# SparkFun_HX711_Load_Cell.net
KiCad netlist of a schematic drawn in EAGLE
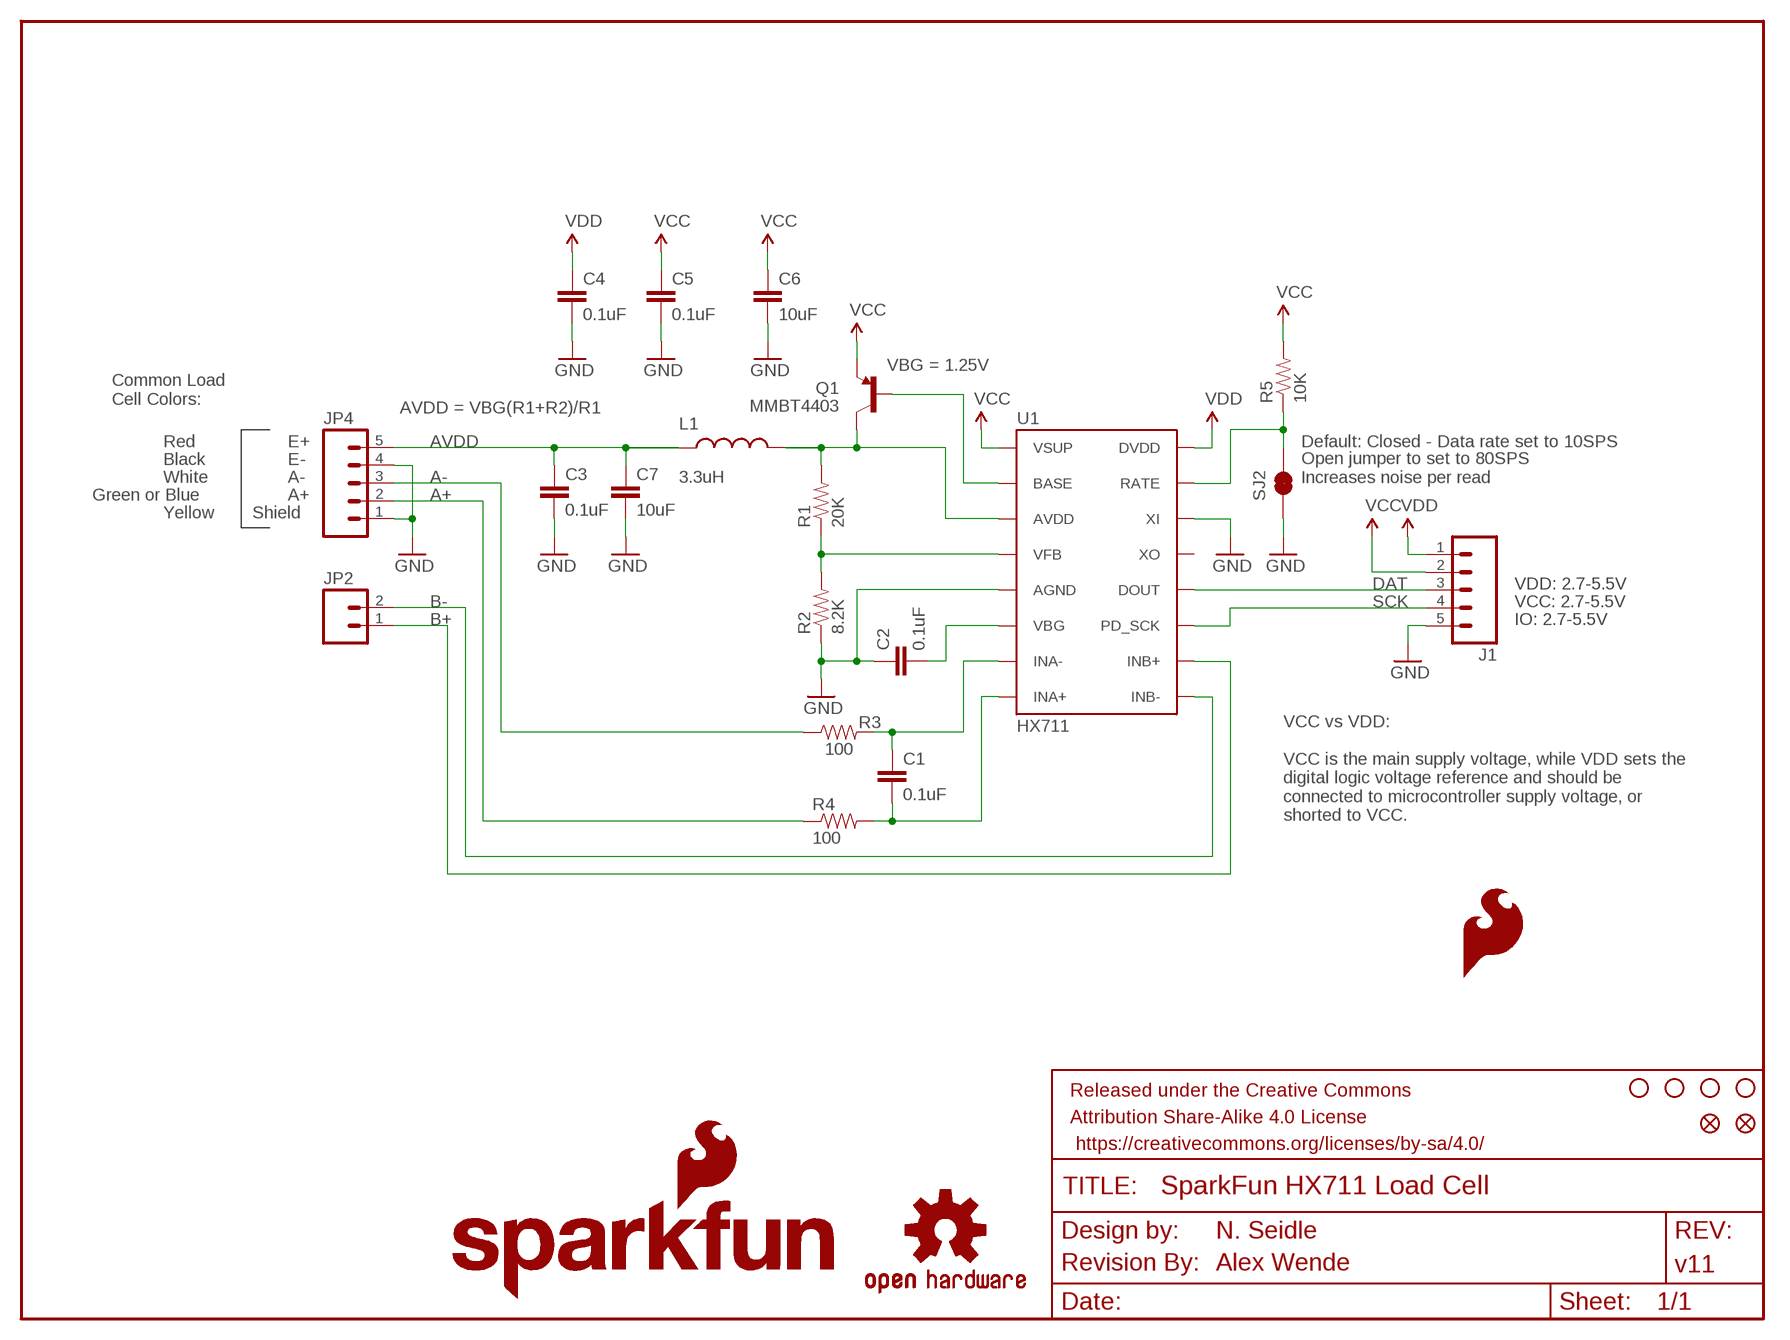
[diagram p0: schematic, sheet 1]

(export (version "E")
  (design (tool "Eeschema 10.0.6"))
  (components
    (comp (ref "C1")
      (value "0.1uF")
      (footprint "eagle-import:0603-CAP")
      (libsource (lib "eagle-import") (part "0.1UF-25V-5%(0603)"))
    )
    (comp (ref "C2")
      (value "0.1uF")
      (footprint "eagle-import:0603-CAP")
      (libsource (lib "eagle-import") (part "0.1UF-25V-5%(0603)"))
    )
    (comp (ref "C3")
      (value "0.1uF")
      (footprint "eagle-import:0603-CAP")
      (libsource (lib "eagle-import") (part "0.1UF-25V-5%(0603)"))
    )
    (comp (ref "C4")
      (value "0.1uF")
      (footprint "eagle-import:0603-CAP")
      (libsource (lib "eagle-import") (part "0.1UF-25V-5%(0603)"))
    )
    (comp (ref "C5")
      (value "0.1uF")
      (footprint "eagle-import:0603-CAP")
      (libsource (lib "eagle-import") (part "0.1UF-25V-5%(0603)"))
    )
    (comp (ref "C6")
      (value "10uF")
      (footprint "eagle-import:1210")
      (libsource (lib "eagle-import") (part "10UF50V20%(1210)"))
    )
    (comp (ref "C7")
      (value "10uF")
      (footprint "eagle-import:1210")
      (libsource (lib "eagle-import") (part "10UF50V20%(1210)"))
    )
    (comp (ref "FID1")
      (value "FIDUCIAL1X2")
      (footprint "eagle-import:FIDUCIAL-1X2")
      (libsource (lib "eagle-import") (part "FIDUCIAL1X2"))
    )
    (comp (ref "FID2")
      (value "FIDUCIAL1X2")
      (footprint "eagle-import:FIDUCIAL-1X2")
      (libsource (lib "eagle-import") (part "FIDUCIAL1X2"))
    )
    (comp (ref "FRAME1")
      (value "FRAME-LETTER")
      (footprint "eagle-import:CREATIVE_COMMONS")
      (fields (field (name "DESIGNER") "N. Seidle") (field (name "VERSION") "v11"))
      (libsource (lib "eagle-import") (part "FRAME-LETTER"))
    )
    (comp (ref "J1")
      (value "M05PTH")
      (footprint "eagle-import:1X05")
      (libsource (lib "eagle-import") (part "M05PTH"))
    )
    (comp (ref "JP2")
      (value "M02PTH")
      (footprint "eagle-import:1X02")
      (libsource (lib "eagle-import") (part "M02PTH"))
    )
    (comp (ref "JP4")
      (value "M05PTH")
      (footprint "eagle-import:1X05")
      (libsource (lib "eagle-import") (part "M05PTH"))
    )
    (comp (ref "L1")
      (value "3.3uH")
      (footprint "eagle-import:0805")
      (libsource (lib "eagle-import") (part "INDUCTOR0805-IND"))
    )
    (comp (ref "LOGO1")
      (value "SFE_LOGO_NAME_FLAME.1_INCH")
      (footprint "eagle-import:SFE_LOGO_NAME_FLAME_.1")
      (libsource (lib "eagle-import") (part "SFE_LOGO_NAME_FLAME.1_INCH"))
    )
    (comp (ref "LOGO3")
      (value "SFE_LOGO_FLAME.1_INCH")
      (footprint "eagle-import:SFE_LOGO_FLAME_.1")
      (libsource (lib "eagle-import") (part "SFE_LOGO_FLAME.1_INCH"))
    )
    (comp (ref "Q1")
      (value "MMBT4403")
      (footprint "eagle-import:SOT23-3")
      (libsource (lib "eagle-import") (part "TRANSISTOR_PNPMMBT4403"))
    )
    (comp (ref "R1")
      (value "20K")
      (footprint "eagle-import:0603-RES")
      (libsource (lib "eagle-import") (part "20KOHM1/10W1%(0603)"))
    )
    (comp (ref "R2")
      (value "8.2K")
      (footprint "eagle-import:0603-RES")
      (libsource (lib "eagle-import") (part "8.2KOHM-1/10W-5%(0603)"))
    )
    (comp (ref "R3")
      (value "100")
      (footprint "eagle-import:0603-RES")
      (libsource (lib "eagle-import") (part "100OHM-1/10W-1%(0603)"))
    )
    (comp (ref "R4")
      (value "100")
      (footprint "eagle-import:0603-RES")
      (libsource (lib "eagle-import") (part "100OHM-1/10W-1%(0603)"))
    )
    (comp (ref "R5")
      (value "10K")
      (footprint "eagle-import:0603-RES")
      (libsource (lib "eagle-import") (part "10KOHM-1/10W-1%(0603)0603"))
    )
    (comp (ref "SJ2")
      (value "JUMPER-PAD-2-NC_BY_TRACE")
      (footprint "eagle-import:PAD-JUMPER-2-NC_BY_TRACE_YES_SILK")
      (libsource (lib "eagle-import") (part "JUMPER-PAD-2-NC_BY_TRACE"))
    )
    (comp (ref "STANDOFF1")
      (value "STAND-OFF")
      (footprint "eagle-import:STAND-OFF")
      (libsource (lib "eagle-import") (part "STAND-OFF"))
    )
    (comp (ref "STANDOFF2")
      (value "STAND-OFF")
      (footprint "eagle-import:STAND-OFF")
      (libsource (lib "eagle-import") (part "STAND-OFF"))
    )
    (comp (ref "STANDOFF3")
      (value "STAND-OFF")
      (footprint "eagle-import:STAND-OFF")
      (libsource (lib "eagle-import") (part "STAND-OFF"))
    )
    (comp (ref "STANDOFF4")
      (value "STAND-OFF")
      (footprint "eagle-import:STAND-OFF")
      (libsource (lib "eagle-import") (part "STAND-OFF"))
    )
    (comp (ref "U$1")
      (value "REVISION")
      (footprint "eagle-import:REVISION")
      (libsource (lib "eagle-import") (part "REVISION"))
    )
    (comp (ref "U1")
      (value "HX711")
      (footprint "eagle-import:SO16")
      (libsource (lib "eagle-import") (part "HX711HX711"))
    )
    (comp (ref "U7")
      (value "OSHW-LOGOS")
      (footprint "eagle-import:OSHW-LOGO-S")
      (libsource (lib "eagle-import") (part "OSHW-LOGOS"))
    )
  )
  (nets
    (net (code "1") (name "/A+") (class "Default")
      (node (ref "JP4") (pin "2") (pinfunction "2_2") (pintype "passive"))
      (node (ref "R4") (pin "1") (pinfunction "1_1") (pintype "passive"))
    )
    (net (code "2") (name "/A-") (class "Default")
      (node (ref "JP4") (pin "3") (pinfunction "3_3") (pintype "passive"))
      (node (ref "R3") (pin "1") (pinfunction "1_1") (pintype "passive"))
    )
    (net (code "3") (name "/AVDD") (class "Default")
      (node (ref "C3") (pin "1") (pinfunction "1_1") (pintype "passive"))
      (node (ref "C7") (pin "1") (pinfunction "1_1") (pintype "passive"))
      (node (ref "JP4") (pin "5") (pinfunction "5_5") (pintype "passive"))
      (node (ref "L1") (pin "1") (pinfunction "1_1") (pintype "passive"))
    )
    (net (code "4") (name "/B+") (class "Default")
      (node (ref "JP2") (pin "1") (pinfunction "1_1") (pintype "passive"))
      (node (ref "U1") (pin "10") (pinfunction "INB+_10") (pintype "bidirectional"))
    )
    (net (code "5") (name "/B-") (class "Default")
      (node (ref "JP2") (pin "2") (pinfunction "2_2") (pintype "passive"))
      (node (ref "U1") (pin "9") (pinfunction "INB-_9") (pintype "bidirectional"))
    )
    (net (code "6") (name "/DAT") (class "Default")
      (node (ref "J1") (pin "3") (pinfunction "3_3") (pintype "passive"))
      (node (ref "U1") (pin "12") (pinfunction "DOUT_12") (pintype "bidirectional"))
    )
    (net (code "7") (name "/SCK") (class "Default")
      (node (ref "J1") (pin "4") (pinfunction "4_4") (pintype "passive"))
      (node (ref "U1") (pin "11") (pinfunction "PD_SCK_11") (pintype "bidirectional"))
    )
    (net (code "8") (name "GND") (class "Default")
      (node (ref "C2") (pin "1") (pinfunction "1_1") (pintype "passive"))
      (node (ref "C3") (pin "2") (pinfunction "2_2") (pintype "passive"))
      (node (ref "C4") (pin "2") (pinfunction "2_2") (pintype "passive"))
      (node (ref "C5") (pin "2") (pinfunction "2_2") (pintype "passive"))
      (node (ref "C6") (pin "2") (pinfunction "2_2") (pintype "passive"))
      (node (ref "C7") (pin "2") (pinfunction "2_2") (pintype "passive"))
      (node (ref "J1") (pin "5") (pinfunction "5_5") (pintype "passive"))
      (node (ref "JP4") (pin "1") (pinfunction "1_1") (pintype "passive"))
      (node (ref "JP4") (pin "4") (pinfunction "4_4") (pintype "passive"))
      (node (ref "R2") (pin "1") (pinfunction "1_1") (pintype "passive"))
      (node (ref "SJ2") (pin "1") (pinfunction "1_1") (pintype "passive"))
      (node (ref "U1") (pin "14") (pinfunction "XI_14") (pintype "bidirectional"))
      (node (ref "U1") (pin "5") (pinfunction "AGND_5") (pintype "bidirectional"))
    )
    (net (code "9") (name "Net-(Q1-B)") (class "Default")
      (node (ref "Q1") (pin "1") (pinfunction "B_1") (pintype "passive"))
      (node (ref "U1") (pin "2") (pinfunction "BASE_2") (pintype "bidirectional"))
    )
    (net (code "10") (name "Net-(Q1-C)") (class "Default")
      (node (ref "L1") (pin "2") (pinfunction "2_2") (pintype "passive"))
      (node (ref "Q1") (pin "3") (pinfunction "C_3") (pintype "passive"))
      (node (ref "R1") (pin "2") (pinfunction "2_2") (pintype "passive"))
      (node (ref "U1") (pin "3") (pinfunction "AVDD_3") (pintype "bidirectional"))
    )
    (net (code "11") (name "Net-(U1-INA+)") (class "Default")
      (node (ref "C1") (pin "2") (pinfunction "2_2") (pintype "passive"))
      (node (ref "R4") (pin "2") (pinfunction "2_2") (pintype "passive"))
      (node (ref "U1") (pin "8") (pinfunction "INA+_8") (pintype "bidirectional"))
    )
    (net (code "12") (name "Net-(U1-INA-)") (class "Default")
      (node (ref "C1") (pin "1") (pinfunction "1_1") (pintype "passive"))
      (node (ref "R3") (pin "2") (pinfunction "2_2") (pintype "passive"))
      (node (ref "U1") (pin "7") (pinfunction "INA-_7") (pintype "bidirectional"))
    )
    (net (code "13") (name "Net-(U1-RATE)") (class "Default")
      (node (ref "R5") (pin "1") (pinfunction "1_1") (pintype "passive"))
      (node (ref "SJ2") (pin "2") (pinfunction "2_2") (pintype "passive"))
      (node (ref "U1") (pin "15") (pinfunction "RATE_15") (pintype "bidirectional"))
    )
    (net (code "14") (name "Net-(U1-VBG)") (class "Default")
      (node (ref "C2") (pin "2") (pinfunction "2_2") (pintype "passive"))
      (node (ref "U1") (pin "6") (pinfunction "VBG_6") (pintype "bidirectional"))
    )
    (net (code "15") (name "Net-(U1-VFB)") (class "Default")
      (node (ref "R1") (pin "1") (pinfunction "1_1") (pintype "passive"))
      (node (ref "R2") (pin "2") (pinfunction "2_2") (pintype "passive"))
      (node (ref "U1") (pin "4") (pinfunction "VFB_4") (pintype "bidirectional"))
    )
    (net (code "16") (name "VCC") (class "Default")
      (node (ref "C5") (pin "1") (pinfunction "1_1") (pintype "passive"))
      (node (ref "C6") (pin "1") (pinfunction "1_1") (pintype "passive"))
      (node (ref "J1") (pin "2") (pinfunction "2_2") (pintype "passive"))
      (node (ref "Q1") (pin "2") (pinfunction "E_2") (pintype "passive"))
      (node (ref "R5") (pin "2") (pinfunction "2_2") (pintype "passive"))
      (node (ref "U1") (pin "1") (pinfunction "VSUP_1") (pintype "bidirectional"))
    )
    (net (code "17") (name "VDD") (class "Default")
      (node (ref "C4") (pin "1") (pinfunction "1_1") (pintype "passive"))
      (node (ref "J1") (pin "1") (pinfunction "1_1") (pintype "passive"))
      (node (ref "U1") (pin "16") (pinfunction "DVDD_16") (pintype "bidirectional"))
    )
    (net (code "18") (name "unconnected-(U1-XO-Pad13)") (class "Default")
      (node (ref "U1") (pin "13") (pinfunction "XO_13") (pintype "bidirectional"))
    )
  )
)
